# SJ2088POE_IMX378.net
KiCad netlist of a schematic drawn in Altium Designer
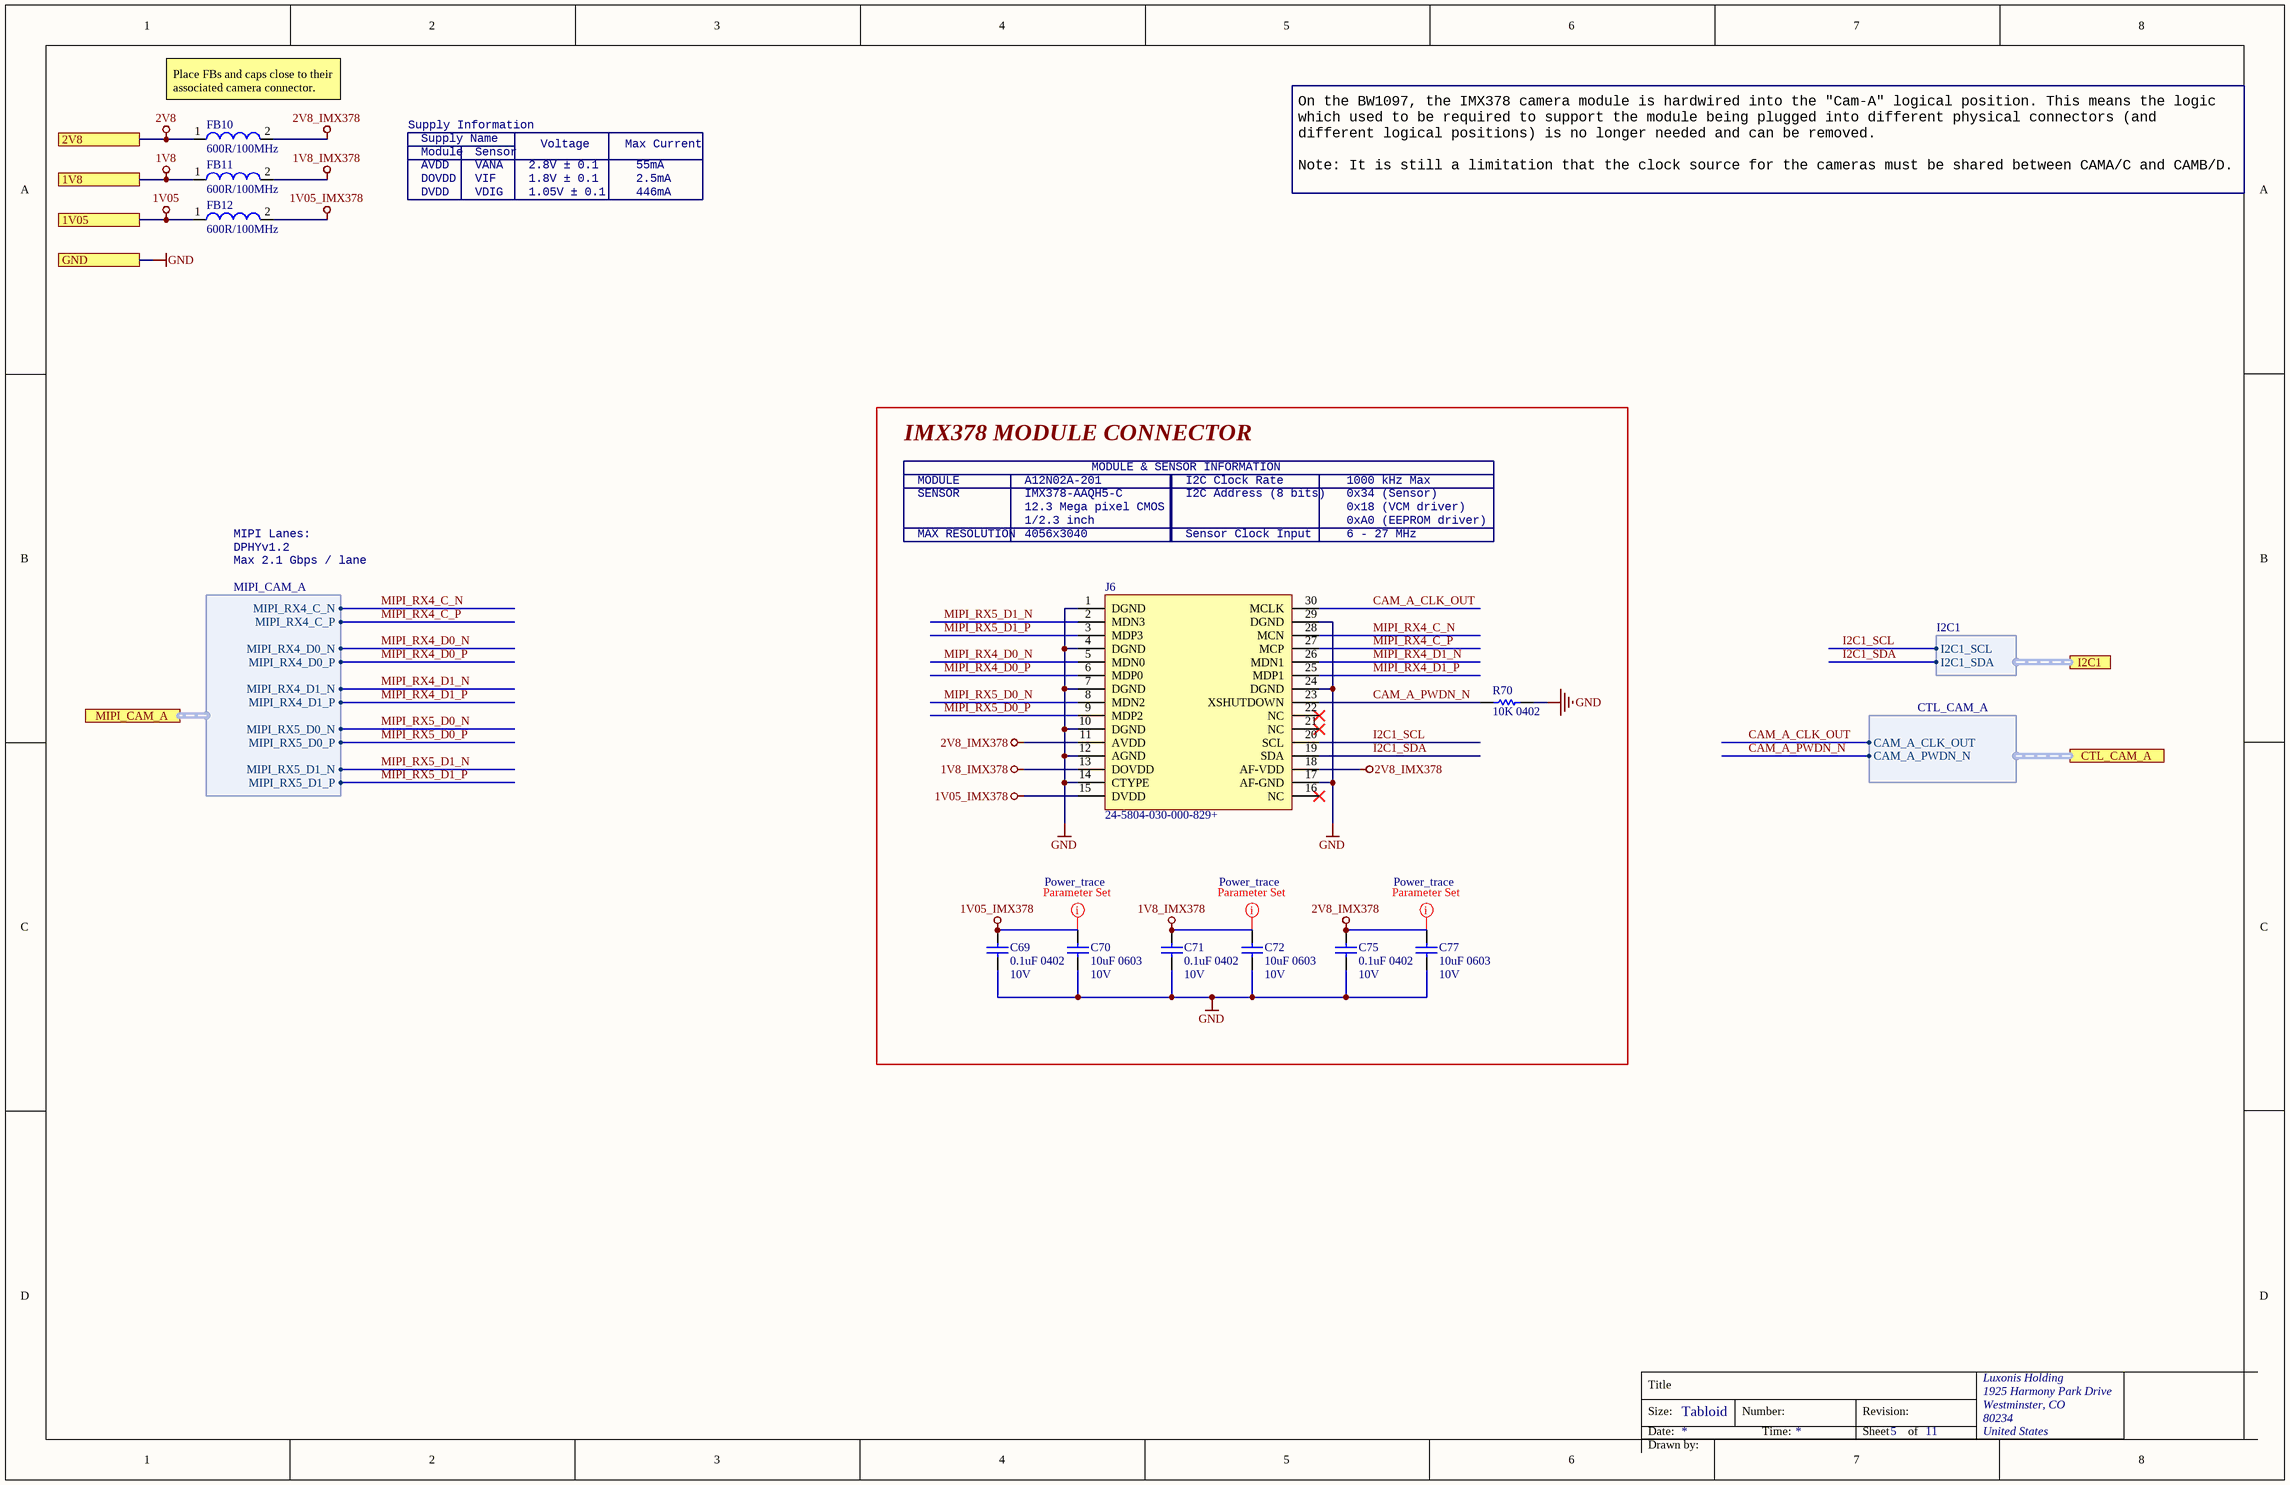
[diagram p0: SJ2088POE_IMX378.SchDoc]

(export (version "E")
  (design (tool "Eeschema 10.0.6"))
  (components
    (comp (ref "C69")
      (value "0.1uF 0402")
      (footprint "CAP_Altium_Vault_Generic:CAPC0402(1005)70_L")
      (description "CAP CER 0.1UF 10V X7R 0402 5%")
      (fields (field (name "TOLERANCE") "5%") (field (name "VOLTAGE RATING") "10V"))
      (libsource (lib "LuxonisMaster") (part "GRM155R71A104JA01D"))
    )
    (comp (ref "C70")
      (value "10uF 0603")
      (footprint "CAP_Altium_Vault_Generic:CAPC0603(1608)100_L")
      (description "CAP CER 10UF 10V X5R 0603 20%")
      (fields (field (name "TOLERANCE") "20%") (field (name "VOLTAGE RATING") "10V"))
      (libsource (lib "LuxonisMaster") (part "GRM188R61A106ME69D"))
    )
    (comp (ref "C71")
      (value "0.1uF 0402")
      (footprint "CAP_Altium_Vault_Generic:CAPC0402(1005)70_L")
      (description "CAP CER 0.1UF 10V X7R 0402 5%")
      (fields (field (name "TOLERANCE") "5%") (field (name "VOLTAGE RATING") "10V"))
      (libsource (lib "LuxonisMaster") (part "GRM155R71A104JA01D"))
    )
    (comp (ref "C72")
      (value "10uF 0603")
      (footprint "CAP_Altium_Vault_Generic:CAPC0603(1608)100_L")
      (description "CAP CER 10UF 10V X5R 0603 20%")
      (fields (field (name "TOLERANCE") "20%") (field (name "VOLTAGE RATING") "10V"))
      (libsource (lib "LuxonisMaster") (part "GRM188R61A106ME69D"))
    )
    (comp (ref "C75")
      (value "0.1uF 0402")
      (footprint "CAP_Altium_Vault_Generic:CAPC0402(1005)70_L")
      (description "CAP CER 0.1UF 10V X7R 0402 5%")
      (fields (field (name "TOLERANCE") "5%") (field (name "VOLTAGE RATING") "10V"))
      (libsource (lib "LuxonisMaster") (part "GRM155R71A104JA01D"))
    )
    (comp (ref "C77")
      (value "10uF 0603")
      (footprint "CAP_Altium_Vault_Generic:CAPC0603(1608)100_L")
      (description "CAP CER 10UF 10V X5R 0603 20%")
      (fields (field (name "TOLERANCE") "20%") (field (name "VOLTAGE RATING") "10V"))
      (libsource (lib "LuxonisMaster") (part "GRM188R61A106ME69D"))
    )
    (comp (ref "FB10")
      (value "600R/100MHz")
      (footprint "LuxonisMaster:2508056017Y2")
      (description "FERRITE BEAD, 0.1OHM, 2A, 0805, 600R/100MHz")
      (fields (field (name "TOLERANCE") "25%"))
      (libsource (lib "LuxonisMaster") (part "2508056017Y2"))
    )
    (comp (ref "FB11")
      (value "600R/100MHz")
      (footprint "LuxonisMaster:2508056017Y2")
      (description "FERRITE BEAD, 0.1OHM, 2A, 0805, 600R/100MHz")
      (fields (field (name "TOLERANCE") "25%"))
      (libsource (lib "LuxonisMaster") (part "2508056017Y2"))
    )
    (comp (ref "FB12")
      (value "600R/100MHz")
      (footprint "LuxonisMaster:2508056017Y2")
      (description "FERRITE BEAD, 0.1OHM, 2A, 0805, 600R/100MHz")
      (fields (field (name "TOLERANCE") "25%"))
      (libsource (lib "LuxonisMaster") (part "2508056017Y2"))
    )
    (comp (ref "J6")
      (value "24-5804-030-000-829+")
      (footprint "BW1098OBC_R3M1E3:A12N02A-201_1.6mmbrd_MatedModule")
      (description "CONN Series 5804 board to board 0.4mm pitch 30 way connector")
      (libsource (lib "BW1098OAK_R0M0E0") (part "A12N02A-201_Connector_(1.6mm_brd)"))
    )
    (comp (ref "R70")
      (value "10K 0402")
      (footprint "RES_Altium_Vault_Generic:RESC0402(1005)_L")
      (fields (field (name "TOLERANCE") "1%"))
      (libsource (lib "LuxonisMaster") (part "RC0402FR-1310KL"))
    )
  )
  (nets
    (net (code "4") (name "/CAM_A_CLK_OUT") (class "Default")
      (node (ref "J6") (pin "30") (pinfunction "MCLK_30") (pintype "passive"))
    )
    (net (code "5") (name "/CAM_A_PWDN_N") (class "Default")
      (node (ref "J6") (pin "23") (pinfunction "XSHUTDOWN_23") (pintype "passive"))
      (node (ref "R70") (pin "1") (pinfunction "1_1") (pintype "passive"))
    )
    (net (code "6") (name "/I2C1_SCL") (class "Default")
      (node (ref "J6") (pin "20") (pinfunction "SCL_20") (pintype "passive"))
    )
    (net (code "7") (name "/I2C1_SDA") (class "Default")
      (node (ref "J6") (pin "19") (pinfunction "SDA_19") (pintype "passive"))
    )
    (net (code "8") (name "/MIPI_RX4_C_N") (class "Default")
      (node (ref "J6") (pin "28") (pinfunction "MCN_28") (pintype "passive"))
    )
    (net (code "9") (name "/MIPI_RX4_C_P") (class "Default")
      (node (ref "J6") (pin "27") (pinfunction "MCP_27") (pintype "passive"))
    )
    (net (code "10") (name "/MIPI_RX4_D0_N") (class "Default")
      (node (ref "J6") (pin "5") (pinfunction "MDN0_5") (pintype "passive"))
    )
    (net (code "11") (name "/MIPI_RX4_D0_P") (class "Default")
      (node (ref "J6") (pin "6") (pinfunction "MDP0_6") (pintype "passive"))
    )
    (net (code "12") (name "/MIPI_RX4_D1_N") (class "Default")
      (node (ref "J6") (pin "26") (pinfunction "MDN1_26") (pintype "passive"))
    )
    (net (code "13") (name "/MIPI_RX4_D1_P") (class "Default")
      (node (ref "J6") (pin "25") (pinfunction "MDP1_25") (pintype "passive"))
    )
    (net (code "14") (name "/MIPI_RX5_D0_N") (class "Default")
      (node (ref "J6") (pin "8") (pinfunction "MDN2_8") (pintype "passive"))
    )
    (net (code "15") (name "/MIPI_RX5_D0_P") (class "Default")
      (node (ref "J6") (pin "9") (pinfunction "MDP2_9") (pintype "passive"))
    )
    (net (code "16") (name "/MIPI_RX5_D1_N") (class "Default")
      (node (ref "J6") (pin "2") (pinfunction "MDN3_2") (pintype "passive"))
    )
    (net (code "17") (name "/MIPI_RX5_D1_P") (class "Default")
      (node (ref "J6") (pin "3") (pinfunction "MDP3_3") (pintype "passive"))
    )
    (net (code "21") (name "1V05") (class "Default")
      (node (ref "FB12") (pin "1") (pinfunction "1_1") (pintype "passive"))
    )
    (net (code "22") (name "1V05_IMX378") (class "Default")
      (node (ref "C69") (pin "2") (pinfunction "2_2") (pintype "passive"))
      (node (ref "C70") (pin "2") (pinfunction "2_2") (pintype "passive"))
      (node (ref "FB12") (pin "2") (pinfunction "2_2") (pintype "passive"))
      (node (ref "J6") (pin "15") (pinfunction "DVDD_15") (pintype "passive"))
    )
    (net (code "23") (name "1V8") (class "Default")
      (node (ref "FB11") (pin "1") (pinfunction "1_1") (pintype "passive"))
    )
    (net (code "24") (name "1V8_IMX378") (class "Default")
      (node (ref "C71") (pin "2") (pinfunction "2_2") (pintype "passive"))
      (node (ref "C72") (pin "2") (pinfunction "2_2") (pintype "passive"))
      (node (ref "FB11") (pin "2") (pinfunction "2_2") (pintype "passive"))
      (node (ref "J6") (pin "13") (pinfunction "DOVDD_13") (pintype "passive"))
    )
    (net (code "25") (name "2V8") (class "Default")
      (node (ref "FB10") (pin "1") (pinfunction "1_1") (pintype "passive"))
    )
    (net (code "26") (name "2V8_IMX378") (class "Default")
      (node (ref "C75") (pin "2") (pinfunction "2_2") (pintype "passive"))
      (node (ref "C77") (pin "2") (pinfunction "2_2") (pintype "passive"))
      (node (ref "FB10") (pin "2") (pinfunction "2_2") (pintype "passive"))
      (node (ref "J6") (pin "11") (pinfunction "AVDD_11") (pintype "passive"))
      (node (ref "J6") (pin "18") (pinfunction "AF-VDD_18") (pintype "passive"))
    )
    (net (code "27") (name "GND") (class "Default")
      (node (ref "C69") (pin "1") (pinfunction "1_1") (pintype "passive"))
      (node (ref "C70") (pin "1") (pinfunction "1_1") (pintype "passive"))
      (node (ref "C71") (pin "1") (pinfunction "1_1") (pintype "passive"))
      (node (ref "C72") (pin "1") (pinfunction "1_1") (pintype "passive"))
      (node (ref "C75") (pin "1") (pinfunction "1_1") (pintype "passive"))
      (node (ref "C77") (pin "1") (pinfunction "1_1") (pintype "passive"))
      (node (ref "J6") (pin "1") (pinfunction "DGND_1") (pintype "passive"))
      (node (ref "J6") (pin "10") (pinfunction "DGND_10") (pintype "passive"))
      (node (ref "J6") (pin "12") (pinfunction "AGND_12") (pintype "passive"))
      (node (ref "J6") (pin "14") (pinfunction "CTYPE_14") (pintype "passive"))
      (node (ref "J6") (pin "17") (pinfunction "AF-GND_17") (pintype "passive"))
      (node (ref "J6") (pin "24") (pinfunction "DGND_24") (pintype "passive"))
      (node (ref "J6") (pin "29") (pinfunction "DGND_29") (pintype "passive"))
      (node (ref "J6") (pin "4") (pinfunction "DGND_4") (pintype "passive"))
      (node (ref "J6") (pin "7") (pinfunction "DGND_7") (pintype "passive"))
      (node (ref "R70") (pin "2") (pinfunction "2_2") (pintype "passive"))
    )
    (net (code "28") (name "unconnected-(J6-NC-Pad16)") (class "Default")
      (node (ref "J6") (pin "16") (pinfunction "NC_16") (pintype "passive+no_connect"))
    )
    (net (code "29") (name "unconnected-(J6-NC-Pad21)") (class "Default")
      (node (ref "J6") (pin "21") (pinfunction "NC_21") (pintype "passive+no_connect"))
    )
    (net (code "30") (name "unconnected-(J6-NC-Pad22)") (class "Default")
      (node (ref "J6") (pin "22") (pinfunction "NC_22") (pintype "passive+no_connect"))
    )
  )
)
